# elekey.net
KiCad netlist of a schematic drawn in EAGLE
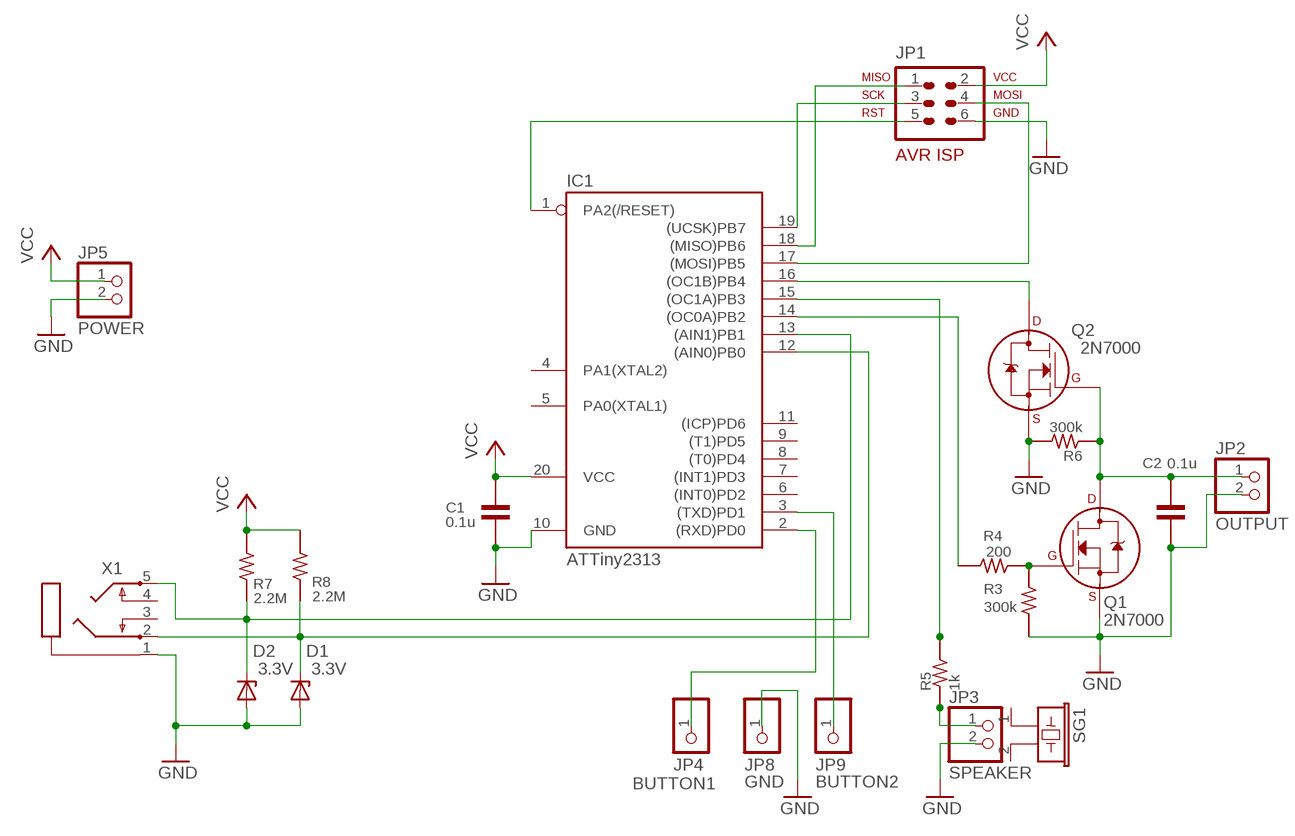
[diagram p0: schematic, sheet 1]

(export (version "E")
  (design (tool "Eeschema 10.0.6"))
  (components
    (comp (ref "C1")
      (value "0.1u")
      (footprint "eagle-import:50-0302-2.54")
      (libsource (lib "eagle-import") (part "C-50V-0302-2.54"))
    )
    (comp (ref "C2")
      (value "0.1u")
      (footprint "eagle-import:50-0302-5.08")
      (libsource (lib "eagle-import") (part "C-50V-0302-5.08"))
    )
    (comp (ref "D1")
      (value "3.3V")
      (footprint "eagle-import:ZDIO-5")
      (libsource (lib "eagle-import") (part "ZENER-DIODEZD-5"))
    )
    (comp (ref "D2")
      (value "3.3V")
      (footprint "eagle-import:ZDIO-5")
      (libsource (lib "eagle-import") (part "ZENER-DIODEZD-5"))
    )
    (comp (ref "IC1")
      (value "ATTiny2313")
      (footprint "eagle-import:DIL20")
      (libsource (lib "eagle-import") (part "TINY2313-P"))
    )
    (comp (ref "JP1")
      (value "AVR-ISP-6VERT")
      (footprint "eagle-import:AVR-ISP-6")
      (libsource (lib "eagle-import") (part "AVR-ISP-6VERT"))
    )
    (comp (ref "JP2")
      (value "OUTPUT")
      (footprint "eagle-import:1X02")
      (libsource (lib "eagle-import") (part "PINHD-1X2"))
    )
    (comp (ref "JP3")
      (value "SPEAKER")
      (footprint "eagle-import:1X02")
      (libsource (lib "eagle-import") (part "PINHD-1X2"))
    )
    (comp (ref "JP4")
      (value "BUTTON1")
      (footprint "eagle-import:1X01")
      (libsource (lib "eagle-import") (part "PINHD-1X1"))
    )
    (comp (ref "JP5")
      (value "POWER")
      (footprint "eagle-import:1X02")
      (libsource (lib "eagle-import") (part "PINHD-1X2"))
    )
    (comp (ref "JP8")
      (value "GND")
      (footprint "eagle-import:1X01")
      (libsource (lib "eagle-import") (part "PINHD-1X1"))
    )
    (comp (ref "JP9")
      (value "BUTTON2")
      (footprint "eagle-import:1X01")
      (libsource (lib "eagle-import") (part "PINHD-1X1"))
    )
    (comp (ref "Q1")
      (value "2N7000")
      (footprint "eagle-import:TO-92")
      (libsource (lib "eagle-import") (part "2N700_TO920"))
    )
    (comp (ref "Q2")
      (value "2N7000")
      (footprint "eagle-import:TO-92")
      (libsource (lib "eagle-import") (part "2N700_TO920"))
    )
    (comp (ref "R3")
      (value "300k")
      (footprint "eagle-import:1_4W-2.54V")
      (libsource (lib "eagle-import") (part "R-1/4W-02.54-V"))
    )
    (comp (ref "R4")
      (value "200")
      (footprint "eagle-import:1_4W-7.62H")
      (libsource (lib "eagle-import") (part "R-1/4W-07.62"))
    )
    (comp (ref "R5")
      (value "1k")
      (footprint "eagle-import:1_4W-5.08V")
      (libsource (lib "eagle-import") (part "R-1/4W-05.08-V"))
    )
    (comp (ref "R6")
      (value "300k")
      (footprint "eagle-import:1_4W-5.08V")
      (libsource (lib "eagle-import") (part "R-1/4W-05.08-V"))
    )
    (comp (ref "R7")
      (value "2.2M")
      (footprint "eagle-import:1_4W-10.16H")
      (libsource (lib "eagle-import") (part "R-1/4W-10.16"))
    )
    (comp (ref "R8")
      (value "2.2M")
      (footprint "eagle-import:1_4W-7.62H")
      (libsource (lib "eagle-import") (part "R-1/4W-07.62"))
    )
    (comp (ref "SG1")
      (value "EFBRD24C411")
      (footprint "eagle-import:EFBRD24C411")
      (libsource (lib "eagle-import") (part "EFB?RD24C411"))
    )
    (comp (ref "X1")
      (value "PG203J")
      (footprint "eagle-import:PG203J")
      (libsource (lib "eagle-import") (part "PG203J"))
    )
  )
  (nets
    (net (code "1") (name "GND") (class "Default")
      (node (ref "C1") (pin "PAD2") (pinfunction "2_PAD2") (pintype "passive"))
      (node (ref "C2") (pin "PAD2") (pinfunction "2_PAD2") (pintype "passive"))
      (node (ref "D1") (pin "A") (pinfunction "A_A") (pintype "passive"))
      (node (ref "D2") (pin "A") (pinfunction "A_A") (pintype "passive"))
      (node (ref "IC1") (pin "10") (pinfunction "GND_10") (pintype "power_in"))
      (node (ref "JP1") (pin "6") (pinfunction "6_6") (pintype "passive"))
      (node (ref "JP2") (pin "2") (pinfunction "2_2") (pintype "passive"))
      (node (ref "JP3") (pin "2") (pinfunction "2_2") (pintype "passive"))
      (node (ref "JP5") (pin "2") (pinfunction "2_2") (pintype "passive"))
      (node (ref "JP8") (pin "1") (pinfunction "1_1") (pintype "passive"))
      (node (ref "Q1") (pin "1") (pinfunction "S_1") (pintype "bidirectional"))
      (node (ref "Q2") (pin "1") (pinfunction "S_1") (pintype "bidirectional"))
      (node (ref "R3") (pin "PAD2") (pinfunction "2_PAD2") (pintype "passive"))
      (node (ref "R6") (pin "PAD2") (pinfunction "2_PAD2") (pintype "passive"))
      (node (ref "X1") (pin "1") (pinfunction "1_1") (pintype "passive"))
    )
    (net (code "2") (name "Net-(C2-1)") (class "Default")
      (node (ref "C2") (pin "PAD1") (pinfunction "1_PAD1") (pintype "passive"))
      (node (ref "JP2") (pin "1") (pinfunction "1_1") (pintype "passive"))
      (node (ref "Q1") (pin "3") (pinfunction "D_3") (pintype "bidirectional"))
      (node (ref "Q2") (pin "2") (pinfunction "G_2") (pintype "tri_state"))
      (node (ref "R6") (pin "PAD1") (pinfunction "1_PAD1") (pintype "passive"))
    )
    (net (code "3") (name "Net-(IC1-(AIN0)PB0)") (class "Default")
      (node (ref "D1") (pin "C") (pinfunction "C_C") (pintype "passive"))
      (node (ref "IC1") (pin "12") (pinfunction "(AIN0)PB0_12") (pintype "bidirectional"))
      (node (ref "R8") (pin "PAD1") (pinfunction "1_PAD1") (pintype "passive"))
      (node (ref "X1") (pin "2") (pinfunction "2_2") (pintype "passive"))
    )
    (net (code "4") (name "Net-(IC1-(AIN1)PB1)") (class "Default")
      (node (ref "D2") (pin "C") (pinfunction "C_C") (pintype "passive"))
      (node (ref "IC1") (pin "13") (pinfunction "(AIN1)PB1_13") (pintype "bidirectional"))
      (node (ref "R7") (pin "PAD1") (pinfunction "1_PAD1") (pintype "passive"))
      (node (ref "X1") (pin "5") (pinfunction "5_5") (pintype "passive"))
    )
    (net (code "5") (name "Net-(IC1-(MISO)PB6)") (class "Default")
      (node (ref "IC1") (pin "18") (pinfunction "(MISO)PB6_18") (pintype "bidirectional"))
      (node (ref "JP1") (pin "1") (pinfunction "1_1") (pintype "passive"))
    )
    (net (code "6") (name "Net-(IC1-(MOSI)PB5)") (class "Default")
      (node (ref "IC1") (pin "17") (pinfunction "(MOSI)PB5_17") (pintype "bidirectional"))
      (node (ref "JP1") (pin "4") (pinfunction "4_4") (pintype "passive"))
    )
    (net (code "7") (name "Net-(IC1-(OC0A)PB2)") (class "Default")
      (node (ref "IC1") (pin "14") (pinfunction "(OC0A)PB2_14") (pintype "bidirectional"))
      (node (ref "R4") (pin "PAD2") (pinfunction "2_PAD2") (pintype "passive"))
    )
    (net (code "8") (name "Net-(IC1-(OC1A)PB3)") (class "Default")
      (node (ref "IC1") (pin "15") (pinfunction "(OC1A)PB3_15") (pintype "bidirectional"))
      (node (ref "R5") (pin "PAD2") (pinfunction "2_PAD2") (pintype "passive"))
    )
    (net (code "9") (name "Net-(IC1-(OC1B)PB4)") (class "Default")
      (node (ref "IC1") (pin "16") (pinfunction "(OC1B)PB4_16") (pintype "bidirectional"))
      (node (ref "Q2") (pin "3") (pinfunction "D_3") (pintype "bidirectional"))
    )
    (net (code "10") (name "Net-(IC1-(RXD)PD0)") (class "Default")
      (node (ref "IC1") (pin "2") (pinfunction "(RXD)PD0_2") (pintype "bidirectional"))
      (node (ref "JP4") (pin "1") (pinfunction "1_1") (pintype "passive"))
    )
    (net (code "11") (name "Net-(IC1-(TXD)PD1)") (class "Default")
      (node (ref "IC1") (pin "3") (pinfunction "(TXD)PD1_3") (pintype "bidirectional"))
      (node (ref "JP9") (pin "1") (pinfunction "1_1") (pintype "passive"))
    )
    (net (code "12") (name "Net-(IC1-(UCSK)PB7)") (class "Default")
      (node (ref "IC1") (pin "19") (pinfunction "(UCSK)PB7_19") (pintype "bidirectional"))
      (node (ref "JP1") (pin "3") (pinfunction "3_3") (pintype "passive"))
    )
    (net (code "13") (name "Net-(IC1-PA2({slash}RESET))") (class "Default")
      (node (ref "IC1") (pin "1") (pinfunction "PA2(/RESET)_1") (pintype "input"))
      (node (ref "JP1") (pin "5") (pinfunction "5_5") (pintype "passive"))
    )
    (net (code "14") (name "Net-(Q1-G)") (class "Default")
      (node (ref "Q1") (pin "2") (pinfunction "G_2") (pintype "tri_state"))
      (node (ref "R3") (pin "PAD1") (pinfunction "1_PAD1") (pintype "passive"))
      (node (ref "R4") (pin "PAD1") (pinfunction "1_PAD1") (pintype "passive"))
    )
    (net (code "15") (name "Net-(R5-1)") (class "Default")
      (node (ref "JP3") (pin "1") (pinfunction "1_1") (pintype "passive"))
      (node (ref "R5") (pin "PAD1") (pinfunction "1_PAD1") (pintype "passive"))
    )
    (net (code "16") (name "VCC") (class "Default")
      (node (ref "C1") (pin "PAD1") (pinfunction "1_PAD1") (pintype "passive"))
      (node (ref "IC1") (pin "20") (pinfunction "VCC_20") (pintype "power_in"))
      (node (ref "JP1") (pin "2") (pinfunction "2_2") (pintype "passive"))
      (node (ref "JP5") (pin "1") (pinfunction "1_1") (pintype "passive"))
      (node (ref "R7") (pin "PAD2") (pinfunction "2_PAD2") (pintype "passive"))
      (node (ref "R8") (pin "PAD2") (pinfunction "2_PAD2") (pintype "passive"))
    )
    (net (code "17") (name "unconnected-(IC1-(ICP)PD6-Pad11)") (class "Default")
      (node (ref "IC1") (pin "11") (pinfunction "(ICP)PD6_11") (pintype "bidirectional"))
    )
    (net (code "18") (name "unconnected-(IC1-(INT0)PD2-Pad6)") (class "Default")
      (node (ref "IC1") (pin "6") (pinfunction "(INT0)PD2_6") (pintype "bidirectional"))
    )
    (net (code "19") (name "unconnected-(IC1-(INT1)PD3-Pad7)") (class "Default")
      (node (ref "IC1") (pin "7") (pinfunction "(INT1)PD3_7") (pintype "bidirectional"))
    )
    (net (code "20") (name "unconnected-(IC1-(T0)PD4-Pad8)") (class "Default")
      (node (ref "IC1") (pin "8") (pinfunction "(T0)PD4_8") (pintype "bidirectional"))
    )
    (net (code "21") (name "unconnected-(IC1-(T1)PD5-Pad9)") (class "Default")
      (node (ref "IC1") (pin "9") (pinfunction "(T1)PD5_9") (pintype "bidirectional"))
    )
    (net (code "22") (name "unconnected-(IC1-PA0(XTAL1)-Pad5)") (class "Default")
      (node (ref "IC1") (pin "5") (pinfunction "PA0(XTAL1)_5") (pintype "bidirectional"))
    )
    (net (code "23") (name "unconnected-(IC1-PA1(XTAL2)-Pad4)") (class "Default")
      (node (ref "IC1") (pin "4") (pinfunction "PA1(XTAL2)_4") (pintype "bidirectional"))
    )
    (net (code "24") (name "unconnected-(SG1-Pad1)") (class "Default")
      (node (ref "SG1") (pin "1") (pinfunction "1_1") (pintype "passive"))
    )
    (net (code "25") (name "unconnected-(SG1-Pad2)") (class "Default")
      (node (ref "SG1") (pin "2") (pinfunction "2_2") (pintype "passive"))
    )
    (net (code "26") (name "unconnected-(X1-Pad3)") (class "Default")
      (node (ref "X1") (pin "3") (pinfunction "3_3") (pintype "passive"))
    )
    (net (code "27") (name "unconnected-(X1-Pad4)") (class "Default")
      (node (ref "X1") (pin "4") (pinfunction "4_4") (pintype "passive"))
    )
  )
)
